# Sheet1.net
KiCad netlist of a schematic drawn in Altium Designer
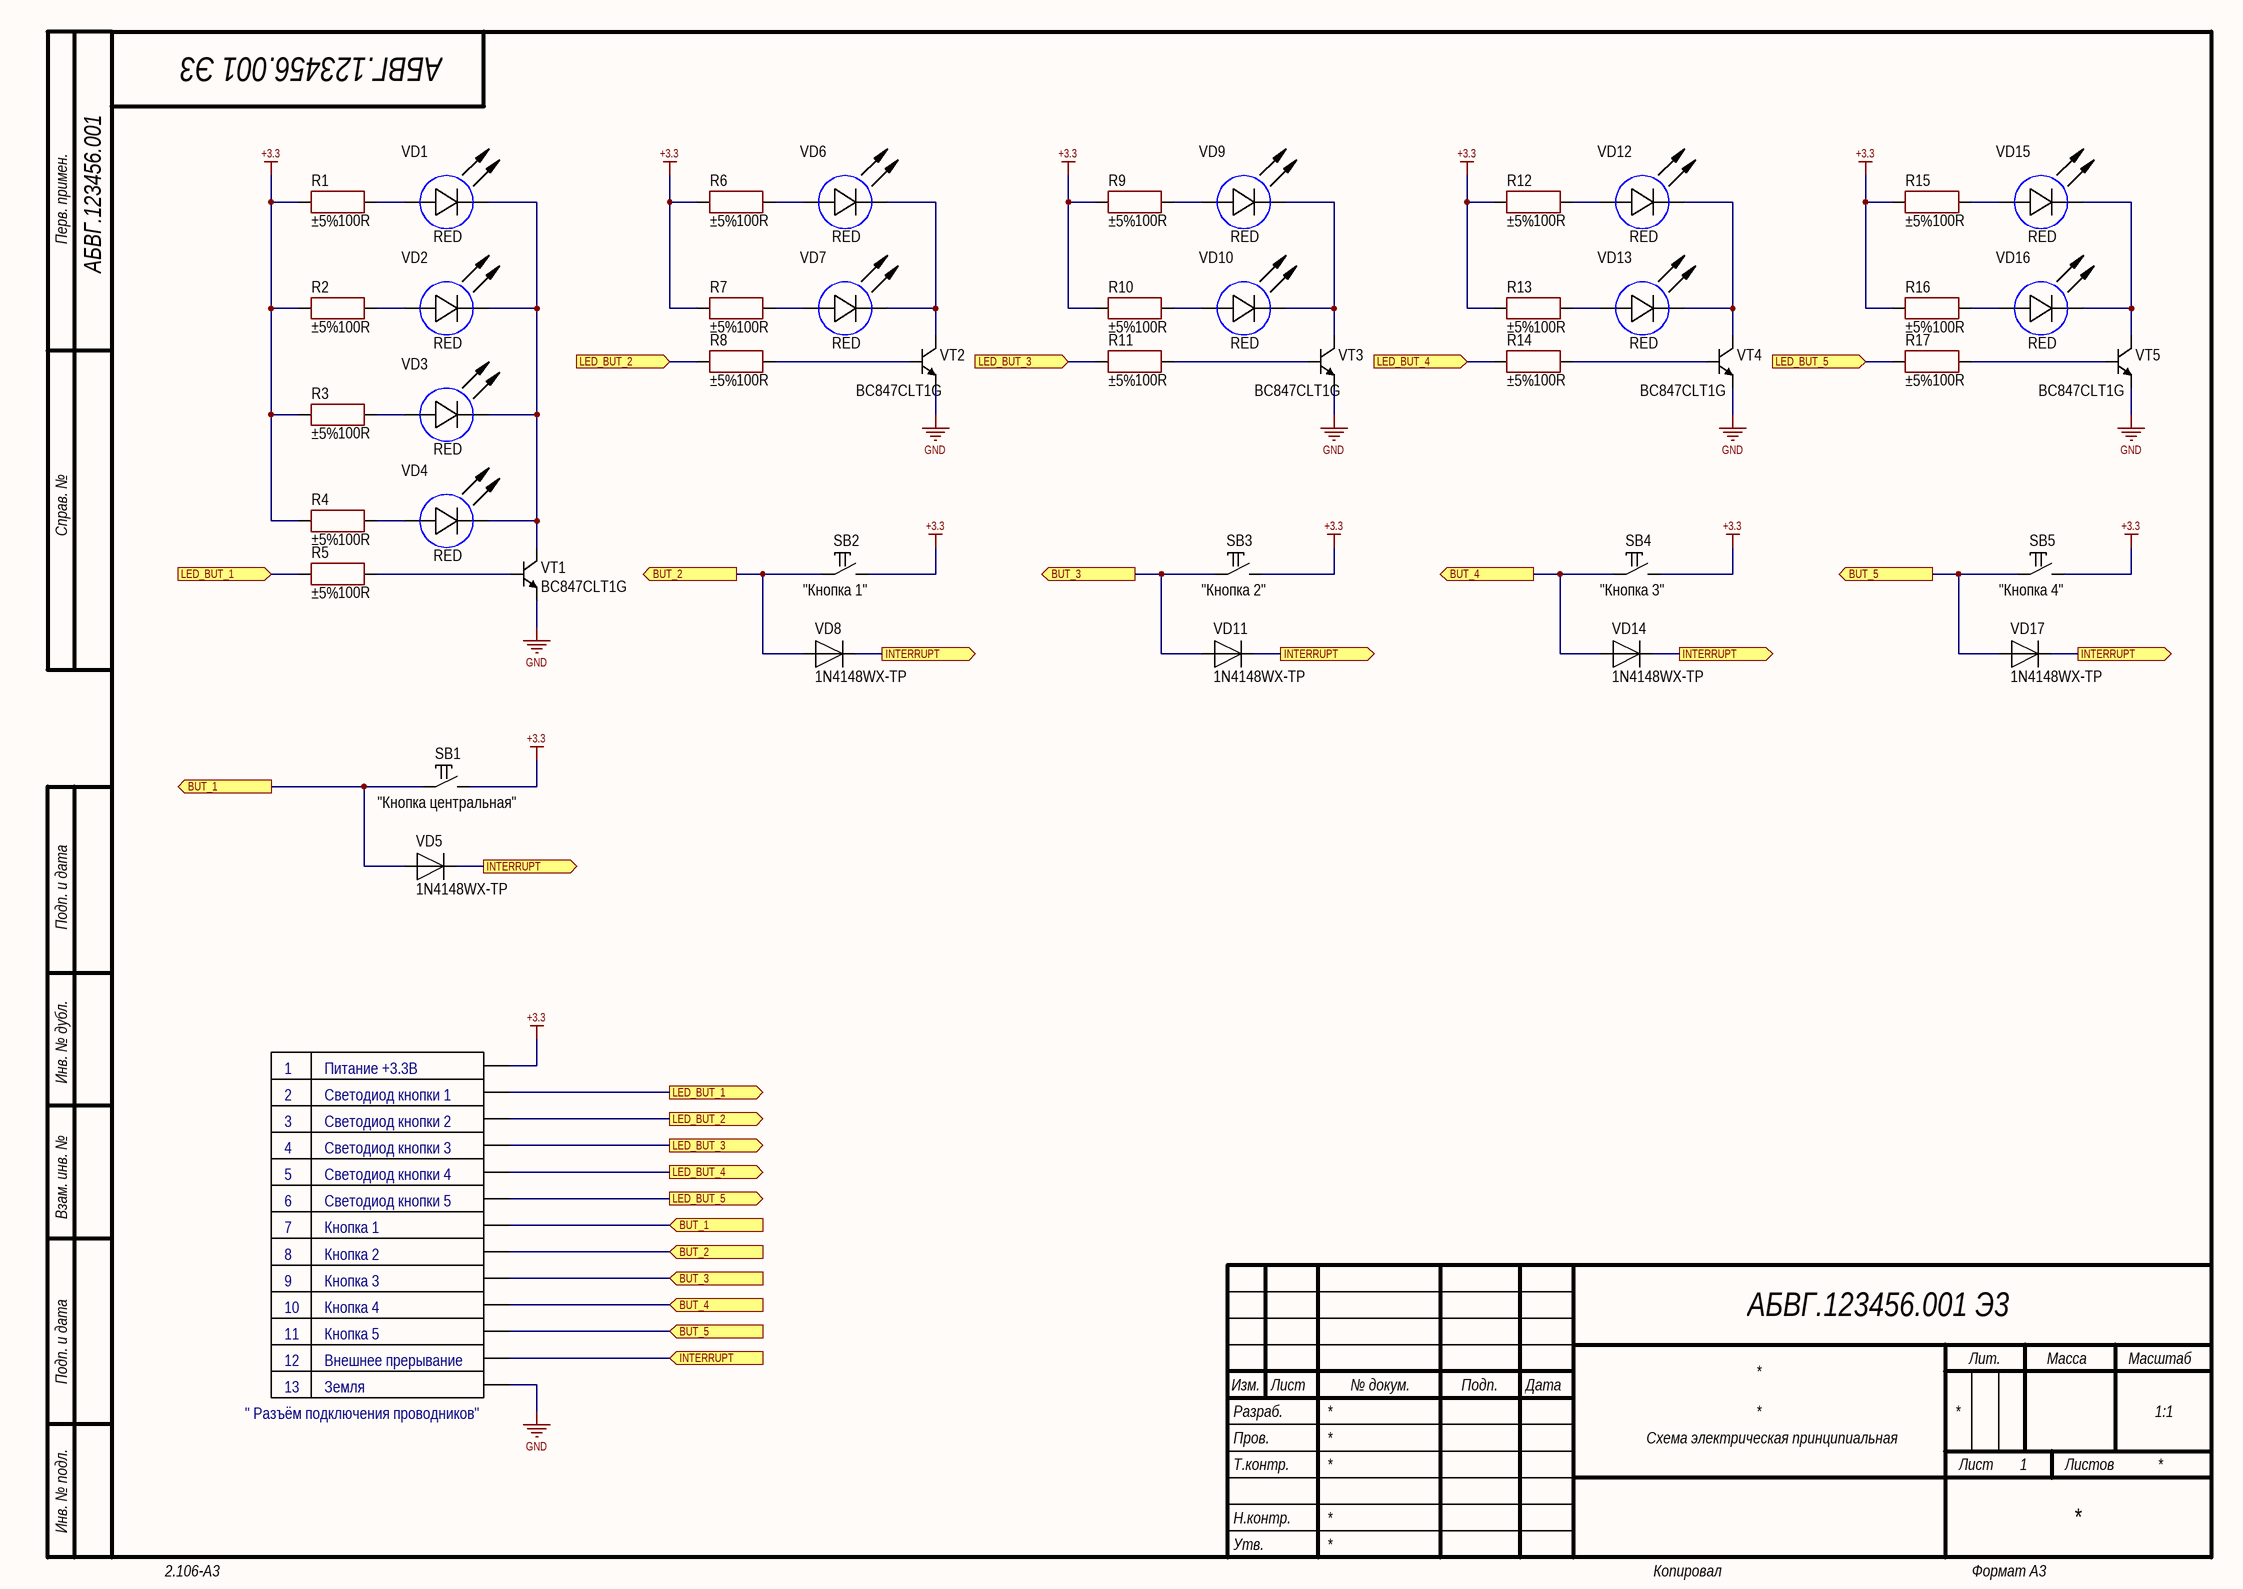
[diagram p0: Sheet1.SchDoc]

(export (version "E")
  (design (tool "Eeschema 10.0.6"))
  (components
    (comp (ref "R1")
      (value "100R")
      (footprint "RES: 0603")
      (fields
        (field (name "MANUFACTURER") "Yageo")
        (field (name "PARTNUMBER") "RC0603JR-07100RL")
        (field (name "VALUEMANUFACTURERPARTNUMBER") "Resistor film, 100R, ±5%, 0603, 0.1W, -55...+125°C")
        (field (name "TOLERANCE") "±5%")
      )
      (libsource (lib "resistor") (part "Resistor_0603"))
    )
    (comp (ref "R2")
      (value "100R")
      (footprint "RES: 0603")
      (fields
        (field (name "MANUFACTURER") "Yageo")
        (field (name "PARTNUMBER") "RC0603JR-07100RL")
        (field (name "VALUEMANUFACTURERPARTNUMBER") "Resistor film, 100R, ±5%, 0603, 0.1W, -55...+125°C")
        (field (name "TOLERANCE") "±5%")
      )
      (libsource (lib "resistor") (part "Resistor_0603"))
    )
    (comp (ref "R3")
      (value "100R")
      (footprint "RES: 0603")
      (fields
        (field (name "MANUFACTURER") "Yageo")
        (field (name "PARTNUMBER") "RC0603JR-07100RL")
        (field (name "VALUEMANUFACTURERPARTNUMBER") "Resistor film, 100R, ±5%, 0603, 0.1W, -55...+125°C")
        (field (name "TOLERANCE") "±5%")
      )
      (libsource (lib "resistor") (part "Resistor_0603"))
    )
    (comp (ref "R4")
      (value "100R")
      (footprint "RES: 0603")
      (fields
        (field (name "MANUFACTURER") "Yageo")
        (field (name "PARTNUMBER") "RC0603JR-07100RL")
        (field (name "VALUEMANUFACTURERPARTNUMBER") "Resistor film, 100R, ±5%, 0603, 0.1W, -55...+125°C")
        (field (name "TOLERANCE") "±5%")
      )
      (libsource (lib "resistor") (part "Resistor_0603"))
    )
    (comp (ref "R5")
      (value "100R")
      (footprint "RES: 0603")
      (fields
        (field (name "MANUFACTURER") "Yageo")
        (field (name "PARTNUMBER") "RC0603JR-07100RL")
        (field (name "VALUEMANUFACTURERPARTNUMBER") "Resistor film, 100R, ±5%, 0603, 0.1W, -55...+125°C")
        (field (name "TOLERANCE") "±5%")
      )
      (libsource (lib "resistor") (part "Resistor_0603"))
    )
    (comp (ref "R6")
      (value "100R")
      (footprint "RES: 0603")
      (fields
        (field (name "MANUFACTURER") "Yageo")
        (field (name "PARTNUMBER") "RC0603JR-07100RL")
        (field (name "VALUEMANUFACTURERPARTNUMBER") "Resistor film, 100R, ±5%, 0603, 0.1W, -55...+125°C")
        (field (name "TOLERANCE") "±5%")
      )
      (libsource (lib "resistor") (part "Resistor_0603"))
    )
    (comp (ref "R7")
      (value "100R")
      (footprint "RES: 0603")
      (fields
        (field (name "MANUFACTURER") "Yageo")
        (field (name "PARTNUMBER") "RC0603JR-07100RL")
        (field (name "VALUEMANUFACTURERPARTNUMBER") "Resistor film, 100R, ±5%, 0603, 0.1W, -55...+125°C")
        (field (name "TOLERANCE") "±5%")
      )
      (libsource (lib "resistor") (part "Resistor_0603"))
    )
    (comp (ref "R8")
      (value "100R")
      (footprint "RES: 0603")
      (fields
        (field (name "MANUFACTURER") "Yageo")
        (field (name "PARTNUMBER") "RC0603JR-07100RL")
        (field (name "VALUEMANUFACTURERPARTNUMBER") "Resistor film, 100R, ±5%, 0603, 0.1W, -55...+125°C")
        (field (name "TOLERANCE") "±5%")
      )
      (libsource (lib "resistor") (part "Resistor_0603"))
    )
    (comp (ref "R9")
      (value "100R")
      (footprint "RES: 0603")
      (fields
        (field (name "MANUFACTURER") "Yageo")
        (field (name "PARTNUMBER") "RC0603JR-07100RL")
        (field (name "VALUEMANUFACTURERPARTNUMBER") "Resistor film, 100R, ±5%, 0603, 0.1W, -55...+125°C")
        (field (name "TOLERANCE") "±5%")
      )
      (libsource (lib "resistor") (part "Resistor_0603"))
    )
    (comp (ref "R10")
      (value "100R")
      (footprint "RES: 0603")
      (fields
        (field (name "MANUFACTURER") "Yageo")
        (field (name "PARTNUMBER") "RC0603JR-07100RL")
        (field (name "VALUEMANUFACTURERPARTNUMBER") "Resistor film, 100R, ±5%, 0603, 0.1W, -55...+125°C")
        (field (name "TOLERANCE") "±5%")
      )
      (libsource (lib "resistor") (part "Resistor_0603"))
    )
    (comp (ref "R11")
      (value "100R")
      (footprint "RES: 0603")
      (fields
        (field (name "MANUFACTURER") "Yageo")
        (field (name "PARTNUMBER") "RC0603JR-07100RL")
        (field (name "VALUEMANUFACTURERPARTNUMBER") "Resistor film, 100R, ±5%, 0603, 0.1W, -55...+125°C")
        (field (name "TOLERANCE") "±5%")
      )
      (libsource (lib "resistor") (part "Resistor_0603"))
    )
    (comp (ref "R12")
      (value "100R")
      (footprint "RES: 0603")
      (fields
        (field (name "MANUFACTURER") "Yageo")
        (field (name "PARTNUMBER") "RC0603JR-07100RL")
        (field (name "VALUEMANUFACTURERPARTNUMBER") "Resistor film, 100R, ±5%, 0603, 0.1W, -55...+125°C")
        (field (name "TOLERANCE") "±5%")
      )
      (libsource (lib "resistor") (part "Resistor_0603"))
    )
    (comp (ref "R13")
      (value "100R")
      (footprint "RES: 0603")
      (fields
        (field (name "MANUFACTURER") "Yageo")
        (field (name "PARTNUMBER") "RC0603JR-07100RL")
        (field (name "VALUEMANUFACTURERPARTNUMBER") "Resistor film, 100R, ±5%, 0603, 0.1W, -55...+125°C")
        (field (name "TOLERANCE") "±5%")
      )
      (libsource (lib "resistor") (part "Resistor_0603"))
    )
    (comp (ref "R14")
      (value "100R")
      (footprint "RES: 0603")
      (fields
        (field (name "MANUFACTURER") "Yageo")
        (field (name "PARTNUMBER") "RC0603JR-07100RL")
        (field (name "VALUEMANUFACTURERPARTNUMBER") "Resistor film, 100R, ±5%, 0603, 0.1W, -55...+125°C")
        (field (name "TOLERANCE") "±5%")
      )
      (libsource (lib "resistor") (part "Resistor_0603"))
    )
    (comp (ref "R15")
      (value "100R")
      (footprint "RES: 0603")
      (fields
        (field (name "MANUFACTURER") "Yageo")
        (field (name "PARTNUMBER") "RC0603JR-07100RL")
        (field (name "VALUEMANUFACTURERPARTNUMBER") "Resistor film, 100R, ±5%, 0603, 0.1W, -55...+125°C")
        (field (name "TOLERANCE") "±5%")
      )
      (libsource (lib "resistor") (part "Resistor_0603"))
    )
    (comp (ref "R16")
      (value "100R")
      (footprint "RES: 0603")
      (fields
        (field (name "MANUFACTURER") "Yageo")
        (field (name "PARTNUMBER") "RC0603JR-07100RL")
        (field (name "VALUEMANUFACTURERPARTNUMBER") "Resistor film, 100R, ±5%, 0603, 0.1W, -55...+125°C")
        (field (name "TOLERANCE") "±5%")
      )
      (libsource (lib "resistor") (part "Resistor_0603"))
    )
    (comp (ref "R17")
      (value "100R")
      (footprint "RES: 0603")
      (fields
        (field (name "MANUFACTURER") "Yageo")
        (field (name "PARTNUMBER") "RC0603JR-07100RL")
        (field (name "VALUEMANUFACTURERPARTNUMBER") "Resistor film, 100R, ±5%, 0603, 0.1W, -55...+125°C")
        (field (name "TOLERANCE") "±5%")
      )
      (libsource (lib "resistor") (part "Resistor_0603"))
    )
    (comp (ref "SB1")
      (value "~")
      (footprint "BUT: 5X5 SMD")
      (fields
        (field (name "MANUFACTURER") "TE Connectivity")
        (field (name "VALUEMANUFACTURERPARTNUMBER") "Tactile button, 6x6mm")
        (field (name "PARTNUMBER") "FSM2JSMAATR")
        (field (name "COMMENTTEXT") "\"Кнопка центральная\"")
      )
      (libsource (lib "electromechanics") (part "Button_tactile"))
    )
    (comp (ref "SB2")
      (value "~")
      (footprint "BUT: 5X5 SMD")
      (fields
        (field (name "MANUFACTURER") "TE Connectivity")
        (field (name "VALUEMANUFACTURERPARTNUMBER") "Tactile button, 6x6mm")
        (field (name "PARTNUMBER") "FSM2JSMAATR")
        (field (name "COMMENTTEXT") "\"Кнопка 1\"")
      )
      (libsource (lib "electromechanics") (part "Button_tactile"))
    )
    (comp (ref "SB3")
      (value "~")
      (footprint "BUT: 5X5 SMD")
      (fields
        (field (name "MANUFACTURER") "TE Connectivity")
        (field (name "VALUEMANUFACTURERPARTNUMBER") "Tactile button, 6x6mm")
        (field (name "PARTNUMBER") "FSM2JSMAATR")
        (field (name "COMMENTTEXT") "\"Кнопка 2\"")
      )
      (libsource (lib "electromechanics") (part "Button_tactile"))
    )
    (comp (ref "SB4")
      (value "~")
      (footprint "BUT: 5X5 SMD")
      (fields
        (field (name "MANUFACTURER") "TE Connectivity")
        (field (name "VALUEMANUFACTURERPARTNUMBER") "Tactile button, 6x6mm")
        (field (name "PARTNUMBER") "FSM2JSMAATR")
        (field (name "COMMENTTEXT") "\"Кнопка 3\"")
      )
      (libsource (lib "electromechanics") (part "Button_tactile"))
    )
    (comp (ref "SB5")
      (value "~")
      (footprint "BUT: 5X5 SMD")
      (fields
        (field (name "MANUFACTURER") "TE Connectivity")
        (field (name "VALUEMANUFACTURERPARTNUMBER") "Tactile button, 6x6mm")
        (field (name "PARTNUMBER") "FSM2JSMAATR")
        (field (name "COMMENTTEXT") "\"Кнопка 4\"")
      )
      (libsource (lib "electromechanics") (part "Button_tactile"))
    )
    (comp (ref "VD1")
      (value "~")
      (footprint "LED: 0805R")
      (fields
        (field (name "VALUEMANUFACTURERPARTNUMBER") "LED, Green, *, *, *, -55...+150°C")
        (field (name "COLOR") "RED")
      )
      (libsource (lib "diode") (part "LED_single"))
    )
    (comp (ref "VD2")
      (value "~")
      (footprint "LED: 0805R")
      (fields
        (field (name "VALUEMANUFACTURERPARTNUMBER") "LED, Green, *, *, *, -55...+150°C")
        (field (name "COLOR") "RED")
      )
      (libsource (lib "diode") (part "LED_single"))
    )
    (comp (ref "VD3")
      (value "~")
      (footprint "LED: 0805R")
      (fields
        (field (name "VALUEMANUFACTURERPARTNUMBER") "LED, Green, *, *, *, -55...+150°C")
        (field (name "COLOR") "RED")
      )
      (libsource (lib "diode") (part "LED_single"))
    )
    (comp (ref "VD4")
      (value "~")
      (footprint "LED: 0805R")
      (fields
        (field (name "VALUEMANUFACTURERPARTNUMBER") "LED, Green, *, *, *, -55...+150°C")
        (field (name "COLOR") "RED")
      )
      (libsource (lib "diode") (part "LED_single"))
    )
    (comp (ref "VD5")
      (value "~")
      (footprint "DIODE: SOD80")
      (fields
        (field (name "MANUFACTURER") "Micro Commercial")
        (field (name "VALUEMANUFACTURERPARTNUMBER") "Single diode, 75V, 150mA, 1V, 4ns, SOD-323, -55...+150°C")
        (field (name "VOLTAGE") "75V")
        (field (name "PARTNUMBER") "1N4148WX-TP")
      )
      (libsource (lib "diode") (part "Diode_single"))
    )
    (comp (ref "VD6")
      (value "~")
      (footprint "LED: 0805R")
      (fields
        (field (name "VALUEMANUFACTURERPARTNUMBER") "LED, Green, *, *, *, -55...+150°C")
        (field (name "COLOR") "RED")
      )
      (libsource (lib "diode") (part "LED_single"))
    )
    (comp (ref "VD7")
      (value "~")
      (footprint "LED: 0805R")
      (fields
        (field (name "VALUEMANUFACTURERPARTNUMBER") "LED, Green, *, *, *, -55...+150°C")
        (field (name "COLOR") "RED")
      )
      (libsource (lib "diode") (part "LED_single"))
    )
    (comp (ref "VD8")
      (value "~")
      (footprint "DIODE: SOD80")
      (fields
        (field (name "MANUFACTURER") "Micro Commercial")
        (field (name "VALUEMANUFACTURERPARTNUMBER") "Single diode, 75V, 150mA, 1V, 4ns, SOD-323, -55...+150°C")
        (field (name "VOLTAGE") "75V")
        (field (name "PARTNUMBER") "1N4148WX-TP")
      )
      (libsource (lib "diode") (part "Diode_single"))
    )
    (comp (ref "VD9")
      (value "~")
      (footprint "LED: 0805R")
      (fields
        (field (name "VALUEMANUFACTURERPARTNUMBER") "LED, Green, *, *, *, -55...+150°C")
        (field (name "COLOR") "RED")
      )
      (libsource (lib "diode") (part "LED_single"))
    )
    (comp (ref "VD10")
      (value "~")
      (footprint "LED: 0805R")
      (fields
        (field (name "VALUEMANUFACTURERPARTNUMBER") "LED, Green, *, *, *, -55...+150°C")
        (field (name "COLOR") "RED")
      )
      (libsource (lib "diode") (part "LED_single"))
    )
    (comp (ref "VD11")
      (value "~")
      (footprint "DIODE: SOD80")
      (fields
        (field (name "MANUFACTURER") "Micro Commercial")
        (field (name "VALUEMANUFACTURERPARTNUMBER") "Single diode, 75V, 150mA, 1V, 4ns, SOD-323, -55...+150°C")
        (field (name "VOLTAGE") "75V")
        (field (name "PARTNUMBER") "1N4148WX-TP")
      )
      (libsource (lib "diode") (part "Diode_single"))
    )
    (comp (ref "VD12")
      (value "~")
      (footprint "LED: 0805R")
      (fields
        (field (name "VALUEMANUFACTURERPARTNUMBER") "LED, Green, *, *, *, -55...+150°C")
        (field (name "COLOR") "RED")
      )
      (libsource (lib "diode") (part "LED_single"))
    )
    (comp (ref "VD13")
      (value "~")
      (footprint "LED: 0805R")
      (fields
        (field (name "VALUEMANUFACTURERPARTNUMBER") "LED, Green, *, *, *, -55...+150°C")
        (field (name "COLOR") "RED")
      )
      (libsource (lib "diode") (part "LED_single"))
    )
    (comp (ref "VD14")
      (value "~")
      (footprint "DIODE: SOD80")
      (fields
        (field (name "MANUFACTURER") "Micro Commercial")
        (field (name "VALUEMANUFACTURERPARTNUMBER") "Single diode, 75V, 150mA, 1V, 4ns, SOD-323, -55...+150°C")
        (field (name "VOLTAGE") "75V")
        (field (name "PARTNUMBER") "1N4148WX-TP")
      )
      (libsource (lib "diode") (part "Diode_single"))
    )
    (comp (ref "VD15")
      (value "~")
      (footprint "LED: 0805R")
      (fields
        (field (name "VALUEMANUFACTURERPARTNUMBER") "LED, Green, *, *, *, -55...+150°C")
        (field (name "COLOR") "RED")
      )
      (libsource (lib "diode") (part "LED_single"))
    )
    (comp (ref "VD16")
      (value "~")
      (footprint "LED: 0805R")
      (fields
        (field (name "VALUEMANUFACTURERPARTNUMBER") "LED, Green, *, *, *, -55...+150°C")
        (field (name "COLOR") "RED")
      )
      (libsource (lib "diode") (part "LED_single"))
    )
    (comp (ref "VD17")
      (value "~")
      (footprint "DIODE: SOD80")
      (fields
        (field (name "MANUFACTURER") "Micro Commercial")
        (field (name "VALUEMANUFACTURERPARTNUMBER") "Single diode, 75V, 150mA, 1V, 4ns, SOD-323, -55...+150°C")
        (field (name "VOLTAGE") "75V")
        (field (name "PARTNUMBER") "1N4148WX-TP")
      )
      (libsource (lib "diode") (part "Diode_single"))
    )
    (comp (ref "VT1")
      (value "~")
      (footprint "SOT23")
      (fields
        (field (name "MANUFACTURER") "ON Semiconductor")
        (field (name "VALUEMANUFACTURERPARTNUMBER") "NPN transistor, 45V, 100mA, 100MHz, 300mW, 0.6V, 420, SOT-23, -55...+125°C")
        (field (name "PARTNUMBER") "BC847CLT1G")
      )
      (libsource (lib "transistor") (part "BJT_NPN_132"))
    )
    (comp (ref "VT2")
      (value "~")
      (footprint "SOT23")
      (fields
        (field (name "MANUFACTURER") "ON Semiconductor")
        (field (name "VALUEMANUFACTURERPARTNUMBER") "NPN transistor, 45V, 100mA, 100MHz, 300mW, 0.6V, 420, SOT-23, -55...+125°C")
        (field (name "PARTNUMBER") "BC847CLT1G")
      )
      (libsource (lib "transistor") (part "BJT_NPN_132"))
    )
    (comp (ref "VT3")
      (value "~")
      (footprint "SOT23")
      (fields
        (field (name "MANUFACTURER") "ON Semiconductor")
        (field (name "VALUEMANUFACTURERPARTNUMBER") "NPN transistor, 45V, 100mA, 100MHz, 300mW, 0.6V, 420, SOT-23, -55...+125°C")
        (field (name "PARTNUMBER") "BC847CLT1G")
      )
      (libsource (lib "transistor") (part "BJT_NPN_132"))
    )
    (comp (ref "VT4")
      (value "~")
      (footprint "SOT23")
      (fields
        (field (name "MANUFACTURER") "ON Semiconductor")
        (field (name "VALUEMANUFACTURERPARTNUMBER") "NPN transistor, 45V, 100mA, 100MHz, 300mW, 0.6V, 420, SOT-23, -55...+125°C")
        (field (name "PARTNUMBER") "BC847CLT1G")
      )
      (libsource (lib "transistor") (part "BJT_NPN_132"))
    )
    (comp (ref "VT5")
      (value "~")
      (footprint "SOT23")
      (fields
        (field (name "MANUFACTURER") "ON Semiconductor")
        (field (name "VALUEMANUFACTURERPARTNUMBER") "NPN transistor, 45V, 100mA, 100MHz, 300mW, 0.6V, 420, SOT-23, -55...+125°C")
        (field (name "PARTNUMBER") "BC847CLT1G")
      )
      (libsource (lib "transistor") (part "BJT_NPN_132"))
    )
  )
  (nets
    (net (code "1") (name "+3.3") (class "Default")
      (node (ref "R1") (pin "1") (pinfunction "1_1") (pintype "passive"))
      (node (ref "R10") (pin "1") (pinfunction "1_1") (pintype "passive"))
      (node (ref "R12") (pin "1") (pinfunction "1_1") (pintype "passive"))
      (node (ref "R13") (pin "1") (pinfunction "1_1") (pintype "passive"))
      (node (ref "R15") (pin "1") (pinfunction "1_1") (pintype "passive"))
      (node (ref "R16") (pin "1") (pinfunction "1_1") (pintype "passive"))
      (node (ref "R2") (pin "1") (pinfunction "1_1") (pintype "passive"))
      (node (ref "R3") (pin "1") (pinfunction "1_1") (pintype "passive"))
      (node (ref "R4") (pin "1") (pinfunction "1_1") (pintype "passive"))
      (node (ref "R6") (pin "1") (pinfunction "1_1") (pintype "passive"))
      (node (ref "R7") (pin "1") (pinfunction "1_1") (pintype "passive"))
      (node (ref "R9") (pin "1") (pinfunction "1_1") (pintype "passive"))
      (node (ref "SB1") (pin "2") (pinfunction "2_2") (pintype "passive"))
      (node (ref "SB2") (pin "2") (pinfunction "2_2") (pintype "passive"))
      (node (ref "SB3") (pin "2") (pinfunction "2_2") (pintype "passive"))
      (node (ref "SB4") (pin "2") (pinfunction "2_2") (pintype "passive"))
      (node (ref "SB5") (pin "2") (pinfunction "2_2") (pintype "passive"))
    )
    (net (code "2") (name "/BUT_1") (class "Default")
      (node (ref "SB1") (pin "1") (pinfunction "1_1") (pintype "passive"))
      (node (ref "VD5") (pin "1") (pinfunction "1_1") (pintype "passive"))
    )
    (net (code "3") (name "/BUT_2") (class "Default")
      (node (ref "SB2") (pin "1") (pinfunction "1_1") (pintype "passive"))
      (node (ref "VD8") (pin "1") (pinfunction "1_1") (pintype "passive"))
    )
    (net (code "4") (name "/BUT_3") (class "Default")
      (node (ref "SB3") (pin "1") (pinfunction "1_1") (pintype "passive"))
      (node (ref "VD11") (pin "1") (pinfunction "1_1") (pintype "passive"))
    )
    (net (code "5") (name "/BUT_4") (class "Default")
      (node (ref "SB4") (pin "1") (pinfunction "1_1") (pintype "passive"))
      (node (ref "VD14") (pin "1") (pinfunction "1_1") (pintype "passive"))
    )
    (net (code "6") (name "/BUT_5") (class "Default")
      (node (ref "SB5") (pin "1") (pinfunction "1_1") (pintype "passive"))
      (node (ref "VD17") (pin "1") (pinfunction "1_1") (pintype "passive"))
    )
    (net (code "7") (name "/INTERRUPT") (class "Default")
      (node (ref "VD11") (pin "2") (pinfunction "2_2") (pintype "passive"))
      (node (ref "VD14") (pin "2") (pinfunction "2_2") (pintype "passive"))
      (node (ref "VD17") (pin "2") (pinfunction "2_2") (pintype "passive"))
      (node (ref "VD5") (pin "2") (pinfunction "2_2") (pintype "passive"))
      (node (ref "VD8") (pin "2") (pinfunction "2_2") (pintype "passive"))
    )
    (net (code "8") (name "/LED_BUT_1") (class "Default")
      (node (ref "R5") (pin "1") (pinfunction "1_1") (pintype "passive"))
    )
    (net (code "9") (name "/LED_BUT_2") (class "Default")
      (node (ref "R8") (pin "1") (pinfunction "1_1") (pintype "passive"))
    )
    (net (code "10") (name "/LED_BUT_3") (class "Default")
      (node (ref "R11") (pin "1") (pinfunction "1_1") (pintype "passive"))
    )
    (net (code "11") (name "/LED_BUT_4") (class "Default")
      (node (ref "R14") (pin "1") (pinfunction "1_1") (pintype "passive"))
    )
    (net (code "12") (name "/LED_BUT_5") (class "Default")
      (node (ref "R17") (pin "1") (pinfunction "1_1") (pintype "passive"))
    )
    (net (code "13") (name "GND") (class "Default")
      (node (ref "VT1") (pin "2") (pinfunction "E_2") (pintype "passive"))
      (node (ref "VT2") (pin "2") (pinfunction "E_2") (pintype "passive"))
      (node (ref "VT3") (pin "2") (pinfunction "E_2") (pintype "passive"))
      (node (ref "VT4") (pin "2") (pinfunction "E_2") (pintype "passive"))
      (node (ref "VT5") (pin "2") (pinfunction "E_2") (pintype "passive"))
    )
    (net (code "14") (name "Net-(VD1-A)") (class "Default")
      (node (ref "R1") (pin "2") (pinfunction "2_2") (pintype "passive"))
      (node (ref "VD1") (pin "1") (pinfunction "A_1") (pintype "passive"))
    )
    (net (code "15") (name "Net-(VD1-C)") (class "Default")
      (node (ref "VD1") (pin "2") (pinfunction "C_2") (pintype "passive"))
      (node (ref "VD2") (pin "2") (pinfunction "C_2") (pintype "passive"))
      (node (ref "VD3") (pin "2") (pinfunction "C_2") (pintype "passive"))
      (node (ref "VD4") (pin "2") (pinfunction "C_2") (pintype "passive"))
      (node (ref "VT1") (pin "3") (pinfunction "C_3") (pintype "passive"))
    )
    (net (code "16") (name "Net-(VD2-A)") (class "Default")
      (node (ref "R2") (pin "2") (pinfunction "2_2") (pintype "passive"))
      (node (ref "VD2") (pin "1") (pinfunction "A_1") (pintype "passive"))
    )
    (net (code "17") (name "Net-(VD3-A)") (class "Default")
      (node (ref "R3") (pin "2") (pinfunction "2_2") (pintype "passive"))
      (node (ref "VD3") (pin "1") (pinfunction "A_1") (pintype "passive"))
    )
    (net (code "18") (name "Net-(VD4-A)") (class "Default")
      (node (ref "R4") (pin "2") (pinfunction "2_2") (pintype "passive"))
      (node (ref "VD4") (pin "1") (pinfunction "A_1") (pintype "passive"))
    )
    (net (code "19") (name "Net-(VD6-A)") (class "Default")
      (node (ref "R6") (pin "2") (pinfunction "2_2") (pintype "passive"))
      (node (ref "VD6") (pin "1") (pinfunction "A_1") (pintype "passive"))
    )
    (net (code "20") (name "Net-(VD6-C)") (class "Default")
      (node (ref "VD6") (pin "2") (pinfunction "C_2") (pintype "passive"))
      (node (ref "VD7") (pin "2") (pinfunction "C_2") (pintype "passive"))
      (node (ref "VT2") (pin "3") (pinfunction "C_3") (pintype "passive"))
    )
    (net (code "21") (name "Net-(VD7-A)") (class "Default")
      (node (ref "R7") (pin "2") (pinfunction "2_2") (pintype "passive"))
      (node (ref "VD7") (pin "1") (pinfunction "A_1") (pintype "passive"))
    )
    (net (code "22") (name "Net-(VD9-A)") (class "Default")
      (node (ref "R9") (pin "2") (pinfunction "2_2") (pintype "passive"))
      (node (ref "VD9") (pin "1") (pinfunction "A_1") (pintype "passive"))
    )
    (net (code "23") (name "Net-(VD10-A)") (class "Default")
      (node (ref "R10") (pin "2") (pinfunction "2_2") (pintype "passive"))
      (node (ref "VD10") (pin "1") (pinfunction "A_1") (pintype "passive"))
    )
    (net (code "24") (name "Net-(VD10-C)") (class "Default")
      (node (ref "VD10") (pin "2") (pinfunction "C_2") (pintype "passive"))
      (node (ref "VD9") (pin "2") (pinfunction "C_2") (pintype "passive"))
      (node (ref "VT3") (pin "3") (pinfunction "C_3") (pintype "passive"))
    )
    (net (code "25") (name "Net-(VD12-A)") (class "Default")
      (node (ref "R12") (pin "2") (pinfunction "2_2") (pintype "passive"))
      (node (ref "VD12") (pin "1") (pinfunction "A_1") (pintype "passive"))
    )
    (net (code "26") (name "Net-(VD12-C)") (class "Default")
      (node (ref "VD12") (pin "2") (pinfunction "C_2") (pintype "passive"))
      (node (ref "VD13") (pin "2") (pinfunction "C_2") (pintype "passive"))
      (node (ref "VT4") (pin "3") (pinfunction "C_3") (pintype "passive"))
    )
    (net (code "27") (name "Net-(VD13-A)") (class "Default")
      (node (ref "R13") (pin "2") (pinfunction "2_2") (pintype "passive"))
      (node (ref "VD13") (pin "1") (pinfunction "A_1") (pintype "passive"))
    )
    (net (code "28") (name "Net-(VD15-A)") (class "Default")
      (node (ref "R15") (pin "2") (pinfunction "2_2") (pintype "passive"))
      (node (ref "VD15") (pin "1") (pinfunction "A_1") (pintype "passive"))
    )
    (net (code "29") (name "Net-(VD15-C)") (class "Default")
      (node (ref "VD15") (pin "2") (pinfunction "C_2") (pintype "passive"))
      (node (ref "VD16") (pin "2") (pinfunction "C_2") (pintype "passive"))
      (node (ref "VT5") (pin "3") (pinfunction "C_3") (pintype "passive"))
    )
    (net (code "30") (name "Net-(VD16-A)") (class "Default")
      (node (ref "R16") (pin "2") (pinfunction "2_2") (pintype "passive"))
      (node (ref "VD16") (pin "1") (pinfunction "A_1") (pintype "passive"))
    )
    (net (code "31") (name "Net-(VT1-B)") (class "Default")
      (node (ref "R5") (pin "2") (pinfunction "2_2") (pintype "passive"))
      (node (ref "VT1") (pin "1") (pinfunction "B_1") (pintype "passive"))
    )
    (net (code "32") (name "Net-(VT2-B)") (class "Default")
      (node (ref "R8") (pin "2") (pinfunction "2_2") (pintype "passive"))
      (node (ref "VT2") (pin "1") (pinfunction "B_1") (pintype "passive"))
    )
    (net (code "33") (name "Net-(VT3-B)") (class "Default")
      (node (ref "R11") (pin "2") (pinfunction "2_2") (pintype "passive"))
      (node (ref "VT3") (pin "1") (pinfunction "B_1") (pintype "passive"))
    )
    (net (code "34") (name "Net-(VT4-B)") (class "Default")
      (node (ref "R14") (pin "2") (pinfunction "2_2") (pintype "passive"))
      (node (ref "VT4") (pin "1") (pinfunction "B_1") (pintype "passive"))
    )
    (net (code "35") (name "Net-(VT5-B)") (class "Default")
      (node (ref "R17") (pin "2") (pinfunction "2_2") (pintype "passive"))
      (node (ref "VT5") (pin "1") (pinfunction "B_1") (pintype "passive"))
    )
  )
)
